# Power_Selection_-_DC-DC.net
KiCad netlist of a schematic drawn in Altium Designer
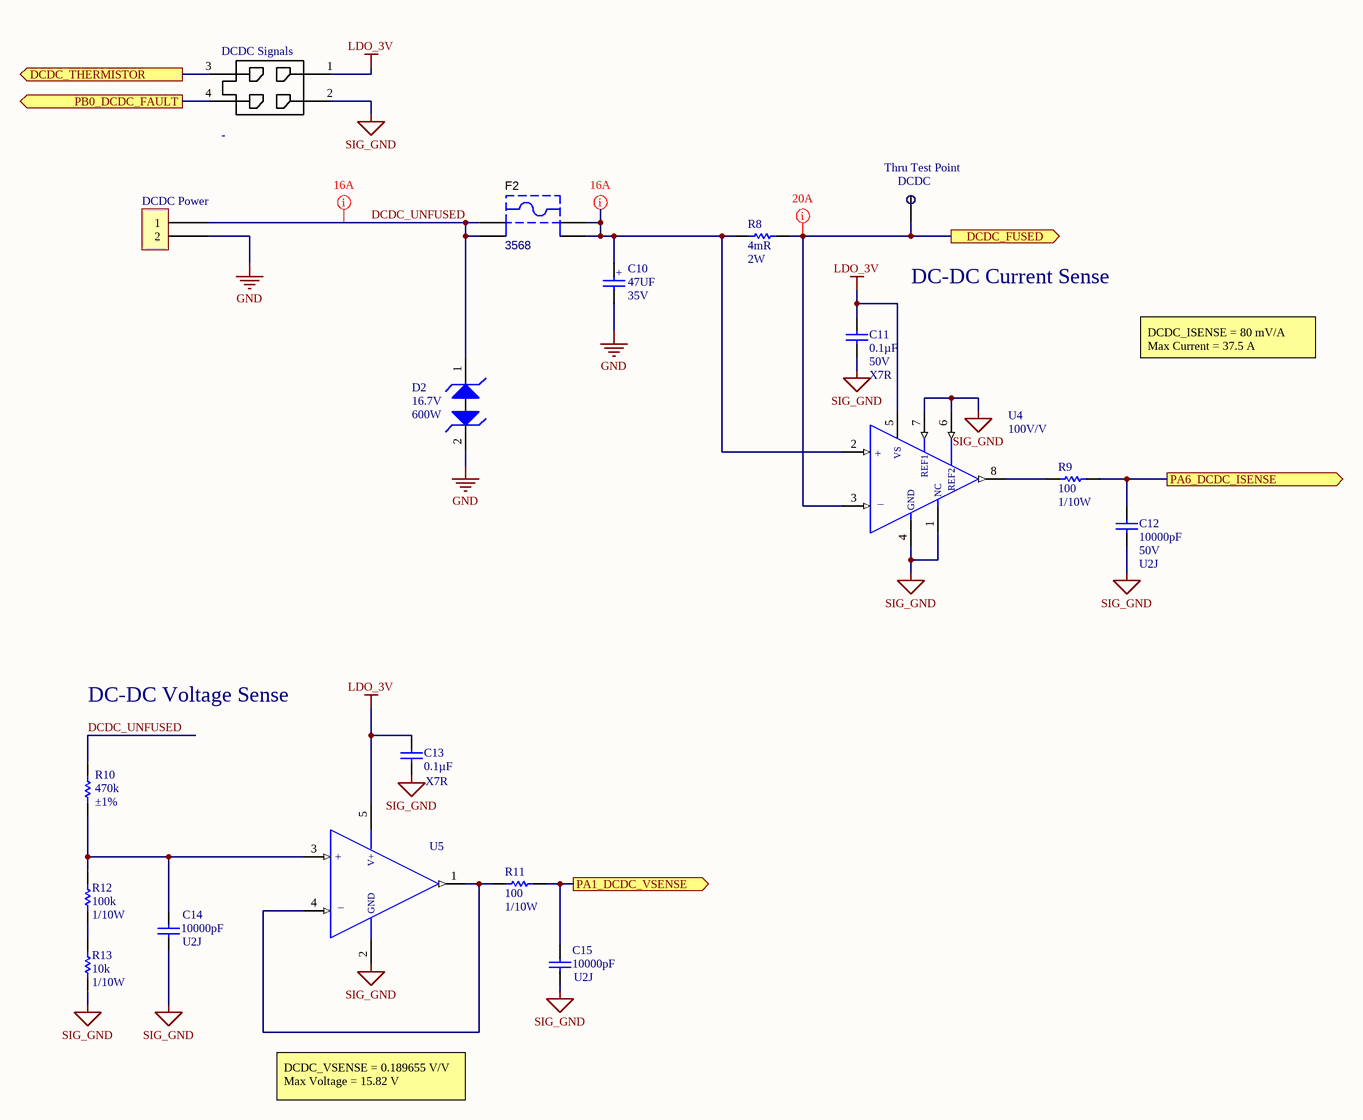
[diagram p0: Power Selection - DC-DC.SchDoc]

(export (version "E")
  (design (tool "Eeschema 10.0.6"))
  (components
    (comp (ref "C10")
      (value "47UF")
      (footprint "CAP ALUM 6.3MM RADIAL SMD")
      (description "47µF 35V Aluminum Electrolytic Capacitors Radial, Can - SMD 1000 Hrs @ 85°C")
      (fields
        (field (name "MANUFACTURER") "Panasonic")
        (field (name "MANUFACTURER PART NUMBER") "EEE-1VA470WP")
        (field (name "VOLTAGE RATING") "35V")
      )
      (libsource (lib "Schematic Diagrams") (part "CAP ALUM 47UF 20% 35V SMD"))
    )
    (comp (ref "C11")
      (value "CAP CER 0.1UF 50V 10% X7R 0603")
      (footprint "CAP, 0603")
      (description "0.10µF ±10% 50V Ceramic Capacitor X7R 0603 (1608 Metric)")
      (fields
        (field (name "TOLERANCE") "±10%")
        (field (name "CAPACITANCE") "0.1µF")
        (field (name "VOLTAGE") "50V")
        (field (name "TEMPERATURE COEFFICIENT") "X7R")
      )
      (libsource (lib "Schematic Diagrams") (part "CAP CER 0.1UF 50V 10% X7R 0603"))
    )
    (comp (ref "C12")
      (value "CAP CER 10nF 50V 5% X7R 0603")
      (footprint "CAP, 0603")
      (description "10000pF ±5% 50V Ceramic Capacitor U2J 0603 (1608 Metric)")
      (fields
        (field (name "TOLERANCE") "±5%")
        (field (name "CAPACITANCE") "10000pF")
        (field (name "VOLTAGE") "50V")
        (field (name "TEMPERATURE COEFFICIENT") "U2J")
      )
      (libsource (lib "Schematic Diagrams") (part "CAP CER 10nF 50V 5% X7R 0603"))
    )
    (comp (ref "C13")
      (value "CAP CER 0.1UF 50V 10% X7R 0603")
      (footprint "CAP, 0603")
      (description "0.10µF ±10% 50V Ceramic Capacitor X7R 0603 (1608 Metric)")
      (fields
        (field (name "TOLERANCE") "±10%")
        (field (name "CAPACITANCE") "0.1µF")
        (field (name "TEMPERATURE COEFFICIENT") "X7R")
        (field (name "VOLTAGE") "50V")
      )
      (libsource (lib "Schematic Diagrams") (part "CAP CER 0.1UF 50V 10% X7R 0603"))
    )
    (comp (ref "C14")
      (value "CAP CER 10nF 50V 5% X7R 0603")
      (footprint "CAP, 0603")
      (description "10000pF ±5% 50V Ceramic Capacitor U2J 0603 (1608 Metric)")
      (fields
        (field (name "TOLERANCE") "±5%")
        (field (name "CAPACITANCE") "10000pF")
        (field (name "TEMPERATURE COEFFICIENT") "U2J")
        (field (name "VOLTAGE") "50V")
      )
      (libsource (lib "Schematic Diagrams") (part "CAP CER 10nF 50V 5% X7R 0603"))
    )
    (comp (ref "C15")
      (value "CAP CER 10nF 50V 5% X7R 0603")
      (footprint "CAP, 0603")
      (description "10000pF ±5% 50V Ceramic Capacitor U2J 0603 (1608 Metric)")
      (fields
        (field (name "TOLERANCE") "±5%")
        (field (name "CAPACITANCE") "10000pF")
        (field (name "TEMPERATURE COEFFICIENT") "U2J")
        (field (name "VOLTAGE") "50V")
      )
      (libsource (lib "Schematic Diagrams") (part "CAP CER 10nF 50V 5% X7R 0603"))
    )
    (comp (ref "D2")
      (value "DIODE TVS 15VWM 24.4VC DO-214AA (SMB)")
      (footprint "DO-214AA Diode")
      (description "TVS DIODE 15VWM 24.4VC SMB")
      (fields (field (name "VOLTAGE - BREAKDOWN (MIN)") "16.7V") (field (name "POWER - PEAK PULSE") "600W"))
      (libsource (lib "Schematic Diagrams") (part "DIODE TVS 15VWM 24.4VC DO-214AA (SMB)"))
    )
    (comp (ref "DCDC")
      (value "Thru Test Point")
      (footprint "Thru Test Point")
      (libsource (lib "Schematic Diagrams") (part "Thru Test Point"))
    )
    (comp (ref "DCDC Power")
      (value "CONN HEADER TE  ELCON Mini 2POS PCB")
      (footprint "CONN HEADER TE  ELCON Mini 2POS PCB-Footprint-1")
      (description "CONN HEADER 2POS PCB")
      (libsource (lib "University of Waterloo - Solar Car Team") (part "CONN HEADER TE  ELCON Mini 2POS PCB"))
    )
    (comp (ref "DCDC Signals")
      (value "CONN 4POS MICRO-FIT 3mm")
      (footprint "CONN 4POS MICROFIT (2x2)")
      (fields
        (field (name "CURRENT RATING") "-")
        (field (name "MANUFACTURER") "Molex, LLC")
        (field (name "MANUFACTURER PART NUMBER") "430450427")
        (field (name "SOURCE") "Schematic Diagrams.SchLib")
      )
      (libsource (lib "University of Waterloo - Solar Car Team") (part "CONN 4POS MICRO-FIT 3mm"))
    )
    (comp (ref "F2")
      (value "3568")
      (footprint "KSTN-3568_V")
      (description "Fuse Holder 20A 500VAC Pin Through Hole")
      (fields (field (name "VOLTAGE") "500V"))
      (libsource (lib "University of Waterloo - Solar Car Team") (part "FUSE_HOLDER-4"))
    )
    (comp (ref "R8")
      (value "RES 4m OHM 1% 2W 2010")
      (footprint "RES 2010")
      (description "4 mOhms ±1% 2W Chip Resistor 2010 (5025 Metric) Automotive AEC-Q200, Current Sense Metal Element")
      (fields (field (name "RESISTANCE") "4mR") (field (name "POWER (WATTS)") "2W"))
      (libsource (lib "Schematic Diagrams") (part "RES 4m OHM 1% 2W 2010"))
    )
    (comp (ref "R9")
      (value "RES 100 OHM 1% 1/10W 0603")
      (footprint "RES, 0603")
      (description "100 Ohm ±1% 0.1W, 1/10W Chip Resistor 0603 (1608 Metric) Moisture Resistant Thick Film")
      (fields
        (field (name "TOLERANCE") "±1%")
        (field (name "RESISTANCE") "100")
        (field (name "POWER") "1/10W")
      )
      (libsource (lib "Schematic Diagrams") (part "RES 100 OHM 1% 1/10W 0603"))
    )
    (comp (ref "R10")
      (value "RES 470K OHM 1% 1/4W 0603")
      (footprint "RES, 0603")
      (description "RES SMD 470K OHM 1% 1/4W 0603")
      (fields (field (name "RESISTANCE") "470k") (field (name "TOLERANCE") "±1%"))
      (libsource (lib "Schematic Diagrams") (part "RES 470K OHM 1% 1/4W 0603"))
    )
    (comp (ref "R11")
      (value "RES 100 OHM 1% 1/10W 0603")
      (footprint "RES, 0603")
      (description "100 Ohm ±1% 0.1W, 1/10W Chip Resistor 0603 (1608 Metric) Moisture Resistant Thick Film")
      (fields
        (field (name "TOLERANCE") "±1%")
        (field (name "RESISTANCE") "100")
        (field (name "POWER") "1/10W")
      )
      (libsource (lib "Schematic Diagrams") (part "RES 100 OHM 1% 1/10W 0603"))
    )
    (comp (ref "R12")
      (value "RES 100K OHM 5% 1/8W 0603")
      (footprint "RES, 0603")
      (description "RES SMD 100K OHM 5% 1/10W 0603")
      (fields
        (field (name "TOLERANCE") "±5%")
        (field (name "RESISTANCE") "100k")
        (field (name "POWER") "1/10W")
      )
      (libsource (lib "Schematic Diagrams") (part "RES 100K OHM 5% 1/8W 0603"))
    )
    (comp (ref "R13")
      (value "RES 10K OHM 1% 1/10W 0603")
      (footprint "RES, 0603")
      (description "RES SMD 10K OHM 1% 1/10W 0603")
      (fields
        (field (name "TOLERANCE") "±1%")
        (field (name "RESISTANCE") "10k")
        (field (name "POWER") "1/10W")
      )
      (libsource (lib "Schematic Diagrams") (part "RES 10K OHM 1% 1/10W 0603"))
    )
    (comp (ref "U4")
      (value "100V/V")
      (footprint "IC CURRENT AMPLIFIER INA240 TSSOP-8")
      (description "Current Sense Amplifier 1 Circuit 8-TSSOP")
      (libsource (lib "Schematic Diagrams") (part "IC CURRENT AMPLIFIER INA240 8-TSSOP"))
    )
    (comp (ref "U5")
      (value "IC OP AMP GEN PURPOSE RR 10MHZ SOT-23-5")
      (footprint "IC OP AMP GP RR 10MHZ SOT-23-5")
      (description "General Purpose Amplifier 1 Circuit Rail-to-Rail SOT-23-5")
      (libsource (lib "Schematic Diagrams") (part "IC OP AMP GEN PURPOSE RR 10MHZ SOT-23-5"))
    )
  )
  (nets
    (net (code "1") (name "/DCDC_FUSED") (class "Default")
      (node (ref "DCDC") (pin "TH_TP") (pinfunction "1_TH_TP") (pintype "passive"))
      (node (ref "R8") (pin "2") (pinfunction "2_2") (pintype "passive"))
      (node (ref "U4") (pin "3") (pinfunction "-IN_3") (pintype "input"))
    )
    (net (code "2") (name "/DCDC_THERMISTOR") (class "Default")
      (node (ref "DCDC Signals") (pin "3") (pinfunction "3_3") (pintype "passive"))
    )
    (net (code "3") (name "/DCDC_UNFUSED") (class "Default")
      (node (ref "D2") (pin "1") (pinfunction "Cathode1_1") (pintype "passive"))
      (node (ref "DCDC Power") (pin "1") (pinfunction "1_1") (pintype "passive"))
      (node (ref "F2") (pin "1") (pinfunction "1_1") (pintype "passive"))
      (node (ref "F2") (pin "2") (pinfunction "2_2") (pintype "passive"))
      (node (ref "R10") (pin "1") (pinfunction "1_1") (pintype "passive"))
    )
    (net (code "4") (name "/PA1_DCDC_VSENSE") (class "Default")
      (node (ref "C15") (pin "1") (pinfunction "1_1") (pintype "passive"))
      (node (ref "R11") (pin "2") (pinfunction "2_2") (pintype "passive"))
    )
    (net (code "5") (name "/PA6_DCDC_ISENSE") (class "Default")
      (node (ref "C12") (pin "1") (pinfunction "1_1") (pintype "passive"))
      (node (ref "R9") (pin "2") (pinfunction "2_2") (pintype "passive"))
    )
    (net (code "6") (name "/PB0_DCDC_FAULT") (class "Default")
      (node (ref "DCDC Signals") (pin "4") (pinfunction "4_4") (pintype "passive"))
    )
    (net (code "7") (name "GND") (class "Default")
      (node (ref "C10") (pin "2") (pinfunction "2_2") (pintype "passive"))
      (node (ref "D2") (pin "2") (pinfunction "Cathode2_2") (pintype "passive"))
      (node (ref "DCDC Power") (pin "2") (pinfunction "2_2") (pintype "passive"))
    )
    (net (code "8") (name "LDO_3V") (class "Default")
      (node (ref "C11") (pin "1") (pinfunction "1_1") (pintype "passive"))
      (node (ref "C13") (pin "1") (pinfunction "1_1") (pintype "passive"))
      (node (ref "DCDC Signals") (pin "1") (pinfunction "1_1") (pintype "passive"))
      (node (ref "U4") (pin "5") (pinfunction "VS_5") (pintype "power_in"))
      (node (ref "U5") (pin "5") (pinfunction "VDD_5") (pintype "power_in"))
    )
    (net (code "9") (name "Net-(R12-Pad2)") (class "Default")
      (node (ref "R12") (pin "2") (pinfunction "2_2") (pintype "passive"))
      (node (ref "R13") (pin "1") (pinfunction "1_1") (pintype "passive"))
    )
    (net (code "10") (name "Net-(U4-+IN)") (class "Default")
      (node (ref "C10") (pin "1") (pinfunction "1_1") (pintype "passive"))
      (node (ref "F2") (pin "3") (pinfunction "3_3") (pintype "passive"))
      (node (ref "F2") (pin "4") (pinfunction "4_4") (pintype "passive"))
      (node (ref "R8") (pin "1") (pinfunction "1_1") (pintype "passive"))
      (node (ref "U4") (pin "2") (pinfunction "+IN_2") (pintype "input"))
    )
    (net (code "11") (name "Net-(U4-OUTPUT)") (class "Default")
      (node (ref "R9") (pin "1") (pinfunction "1_1") (pintype "passive"))
      (node (ref "U4") (pin "8") (pinfunction "OUTPUT_8") (pintype "output"))
    )
    (net (code "12") (name "Net-(U5-+IN)") (class "Default")
      (node (ref "C14") (pin "1") (pinfunction "1_1") (pintype "passive"))
      (node (ref "R10") (pin "2") (pinfunction "2_2") (pintype "passive"))
      (node (ref "R12") (pin "1") (pinfunction "1_1") (pintype "passive"))
      (node (ref "U5") (pin "3") (pinfunction "+IN_3") (pintype "input"))
    )
    (net (code "13") (name "Net-(U5--IN)") (class "Default")
      (node (ref "R11") (pin "1") (pinfunction "1_1") (pintype "passive"))
      (node (ref "U5") (pin "1") (pinfunction "OUTPUT_1") (pintype "output"))
      (node (ref "U5") (pin "4") (pinfunction "-IN_4") (pintype "input"))
    )
    (net (code "14") (name "SIG_GND") (class "Default")
      (node (ref "C11") (pin "2") (pinfunction "2_2") (pintype "passive"))
      (node (ref "C12") (pin "2") (pinfunction "2_2") (pintype "passive"))
      (node (ref "C13") (pin "2") (pinfunction "2_2") (pintype "passive"))
      (node (ref "C14") (pin "2") (pinfunction "2_2") (pintype "passive"))
      (node (ref "C15") (pin "2") (pinfunction "2_2") (pintype "passive"))
      (node (ref "DCDC Signals") (pin "2") (pinfunction "2_2") (pintype "passive"))
      (node (ref "R13") (pin "2") (pinfunction "2_2") (pintype "passive"))
      (node (ref "U4") (pin "1") (pinfunction "NC_1") (pintype "power_in"))
      (node (ref "U4") (pin "4") (pinfunction "GND_4") (pintype "power_in"))
      (node (ref "U4") (pin "6") (pinfunction "REF2_6") (pintype "input"))
      (node (ref "U4") (pin "7") (pinfunction "REF1_7") (pintype "input"))
      (node (ref "U5") (pin "2") (pinfunction "VSS_2") (pintype "power_in"))
    )
  )
)
